# CPU_CIRCUIT.net
KiCad netlist of a schematic drawn in Altium Designer
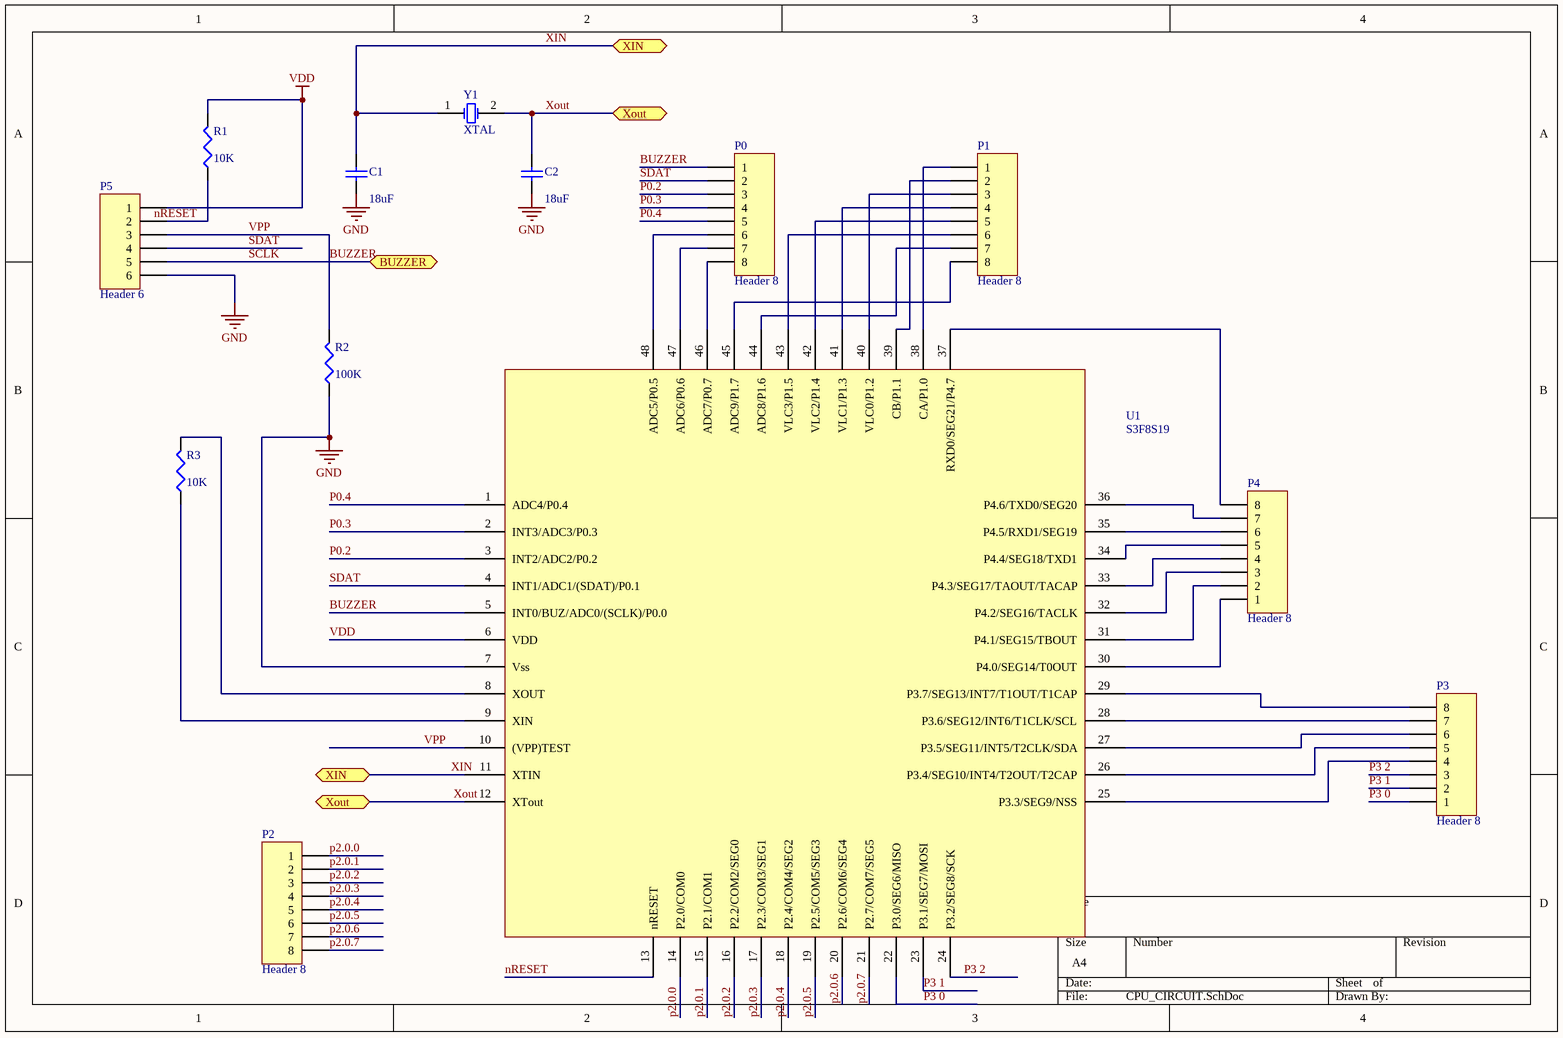
[diagram p0: CPU_CIRCUIT.SchDoc]

(export (version "E")
  (design (tool "Eeschema 10.0.6"))
  (components
    (comp (ref "C1")
      (value "18uF")
      (footprint "1608[0603]")
      (description "Capacitor (Semiconductor SIM Model)")
      (fields (field (name "Comment") "Cap Semi") (field (name "PUBLISHER") "Altium Limited"))
      (libsource (lib "Miscellaneous Devices") (part "Cap Semi"))
    )
    (comp (ref "C2")
      (value "18uF")
      (footprint "1608[0603]")
      (description "Capacitor (Semiconductor SIM Model)")
      (fields (field (name "Comment") "Cap Semi") (field (name "PUBLISHER") "Altium Limited"))
      (libsource (lib "Miscellaneous Devices") (part "Cap Semi"))
    )
    (comp (ref "P0")
      (value "Header 8")
      (footprint "HDR1X8")
      (description "Header, 8-Pin")
      (fields (field (name "PUBLISHER") "Altium Limited"))
      (libsource (lib "") (part "Header 8_1"))
    )
    (comp (ref "P1")
      (value "Header 8")
      (footprint "HDR1X8")
      (description "Header, 8-Pin")
      (fields (field (name "PUBLISHER") "Altium Limited"))
      (libsource (lib "") (part "Header 8_1"))
    )
    (comp (ref "P2")
      (value "Header 8")
      (footprint "HDR1X8")
      (description "Header, 8-Pin")
      (fields (field (name "PUBLISHER") "Altium Limited"))
      (libsource (lib "") (part "Header 8_2"))
    )
    (comp (ref "P3")
      (value "Header 8")
      (footprint "HDR1X8")
      (description "Header, 8-Pin")
      (fields (field (name "PUBLISHER") "Altium Limited"))
      (libsource (lib "Miscellaneous Connectors") (part "Header 8"))
    )
    (comp (ref "P4")
      (value "Header 8")
      (footprint "HDR1X8")
      (description "Header, 8-Pin")
      (fields (field (name "PUBLISHER") "Altium Limited"))
      (libsource (lib "Miscellaneous Connectors") (part "Header 8"))
    )
    (comp (ref "P5")
      (value "Header 6")
      (footprint "HDR1X6")
      (description "Header, 6-Pin")
      (fields (field (name "PUBLISHER") "Altium Limited"))
      (libsource (lib "Miscellaneous Connectors") (part "Header 6"))
    )
    (comp (ref "R1")
      (value "10K")
      (footprint "J1-0603")
      (description "Resistor")
      (fields (field (name "Comment") "Res3") (field (name "PUBLISHER") "Altium Limited"))
      (libsource (lib "Miscellaneous Devices") (part "Res3"))
    )
    (comp (ref "R2")
      (value "100K")
      (footprint "J1-0603")
      (description "Resistor")
      (fields (field (name "Comment") "Res3") (field (name "PUBLISHER") "Altium Limited"))
      (libsource (lib "Miscellaneous Devices") (part "Res3"))
    )
    (comp (ref "R3")
      (value "10K")
      (footprint "J1-0603")
      (description "Resistor")
      (fields (field (name "Comment") "Res3") (field (name "PUBLISHER") "Altium Limited"))
      (libsource (lib "Miscellaneous Devices") (part "Res3"))
    )
    (comp (ref "U1")
      (value "S3F8S19")
      (footprint "QFP75P1335X1335X230-48N")
      (libsource (lib "IOT_SCh") (part "S3F8S19"))
    )
    (comp (ref "Y1")
      (value "XTAL")
      (footprint "R38")
      (description "Crystal Oscillator")
      (fields (field (name "PUBLISHER") "Altium Limited"))
      (libsource (lib "Miscellaneous Devices") (part "XTAL"))
    )
  )
  (nets
    (net (code "1") (name "/BUZZER") (class "Default")
      (node (ref "P0") (pin "1") (pinfunction "1_1") (pintype "passive"))
      (node (ref "P5") (pin "3") (pinfunction "3_3") (pintype "passive"))
      (node (ref "P5") (pin "5") (pinfunction "5_5") (pintype "passive"))
      (node (ref "R2") (pin "2") (pinfunction "2_2") (pintype "passive"))
      (node (ref "U1") (pin "10") (pinfunction "(VPP)TEST_10") (pintype "passive"))
      (node (ref "U1") (pin "5") (pinfunction "INT0/BUZ/ADC0/(SCLK)/P0.0_5") (pintype "passive"))
    )
    (net (code "2") (name "/P0.2") (class "Default")
      (node (ref "P0") (pin "3") (pinfunction "3_3") (pintype "passive"))
      (node (ref "U1") (pin "3") (pinfunction "INT2/ADC2/P0.2_3") (pintype "passive"))
    )
    (net (code "3") (name "/P0.3") (class "Default")
      (node (ref "P0") (pin "4") (pinfunction "4_4") (pintype "passive"))
      (node (ref "U1") (pin "2") (pinfunction "INT3/ADC3/P0.3_2") (pintype "passive"))
    )
    (net (code "4") (name "/P0.4") (class "Default")
      (node (ref "P0") (pin "5") (pinfunction "5_5") (pintype "passive"))
      (node (ref "U1") (pin "1") (pinfunction "ADC4/P0.4_1") (pintype "passive"))
    )
    (net (code "5") (name "/P3 0") (class "Default")
      (node (ref "P3") (pin "1") (pinfunction "1_1") (pintype "passive"))
      (node (ref "U1") (pin "22") (pinfunction "P3.0/SEG6/MISO_22") (pintype "passive"))
    )
    (net (code "6") (name "/P3 1") (class "Default")
      (node (ref "P3") (pin "2") (pinfunction "2_2") (pintype "passive"))
      (node (ref "U1") (pin "23") (pinfunction "P3.1/SEG7/MOSI_23") (pintype "passive"))
    )
    (net (code "7") (name "/P3 2") (class "Default")
      (node (ref "P3") (pin "3") (pinfunction "3_3") (pintype "passive"))
      (node (ref "U1") (pin "24") (pinfunction "P3.2/SEG8/SCK_24") (pintype "passive"))
    )
    (net (code "8") (name "/SDAT") (class "Default")
      (node (ref "P0") (pin "2") (pinfunction "2_2") (pintype "passive"))
      (node (ref "P5") (pin "4") (pinfunction "4_4") (pintype "passive"))
      (node (ref "U1") (pin "4") (pinfunction "INT1/ADC1/(SDAT)/P0.1_4") (pintype "passive"))
    )
    (net (code "9") (name "/XIN") (class "Default")
      (node (ref "C1") (pin "2") (pinfunction "2_2") (pintype "passive"))
      (node (ref "U1") (pin "11") (pinfunction "XTIN_11") (pintype "passive"))
      (node (ref "Y1") (pin "1") (pinfunction "OSC1_1") (pintype "passive"))
    )
    (net (code "10") (name "/Xout") (class "Default")
      (node (ref "C2") (pin "2") (pinfunction "2_2") (pintype "passive"))
      (node (ref "U1") (pin "12") (pinfunction "XTout_12") (pintype "passive"))
      (node (ref "Y1") (pin "2") (pinfunction "OSC2_2") (pintype "passive"))
    )
    (net (code "11") (name "/nRESET") (class "Default")
      (node (ref "U1") (pin "13") (pinfunction "nRESET_13") (pintype "passive"))
    )
    (net (code "12") (name "/p2.0.0") (class "Default")
      (node (ref "P2") (pin "1") (pinfunction "1_1") (pintype "passive"))
      (node (ref "U1") (pin "14") (pinfunction "P2.0/COM0_14") (pintype "passive"))
    )
    (net (code "13") (name "/p2.0.1") (class "Default")
      (node (ref "P2") (pin "2") (pinfunction "2_2") (pintype "passive"))
      (node (ref "U1") (pin "15") (pinfunction "P2.1/COM1_15") (pintype "passive"))
    )
    (net (code "14") (name "/p2.0.2") (class "Default")
      (node (ref "P2") (pin "3") (pinfunction "3_3") (pintype "passive"))
      (node (ref "U1") (pin "16") (pinfunction "P2.2/COM2/SEG0_16") (pintype "passive"))
    )
    (net (code "15") (name "/p2.0.3") (class "Default")
      (node (ref "P2") (pin "4") (pinfunction "4_4") (pintype "passive"))
      (node (ref "U1") (pin "17") (pinfunction "P2.3/COM3/SEG1_17") (pintype "passive"))
    )
    (net (code "16") (name "/p2.0.4") (class "Default")
      (node (ref "P2") (pin "5") (pinfunction "5_5") (pintype "passive"))
      (node (ref "U1") (pin "18") (pinfunction "P2.4/COM4/SEG2_18") (pintype "passive"))
    )
    (net (code "17") (name "/p2.0.5") (class "Default")
      (node (ref "P2") (pin "6") (pinfunction "6_6") (pintype "passive"))
      (node (ref "U1") (pin "19") (pinfunction "P2.5/COM5/SEG3_19") (pintype "passive"))
    )
    (net (code "18") (name "/p2.0.6") (class "Default")
      (node (ref "P2") (pin "7") (pinfunction "7_7") (pintype "passive"))
      (node (ref "U1") (pin "20") (pinfunction "P2.6/COM6/SEG4_20") (pintype "passive"))
    )
    (net (code "19") (name "/p2.0.7") (class "Default")
      (node (ref "P2") (pin "8") (pinfunction "8_8") (pintype "passive"))
      (node (ref "U1") (pin "21") (pinfunction "P2.7/COM7/SEG5_21") (pintype "passive"))
    )
    (net (code "20") (name "GND") (class "Default")
      (node (ref "C1") (pin "1") (pinfunction "1_1") (pintype "passive"))
      (node (ref "C2") (pin "1") (pinfunction "1_1") (pintype "passive"))
      (node (ref "P5") (pin "6") (pinfunction "6_6") (pintype "passive"))
      (node (ref "R2") (pin "1") (pinfunction "1_1") (pintype "passive"))
      (node (ref "U1") (pin "7") (pinfunction "Vss_7") (pintype "passive"))
    )
    (net (code "21") (name "Net-(P5-Pad2)") (class "Default")
      (node (ref "P5") (pin "2") (pinfunction "2_2") (pintype "passive"))
      (node (ref "R1") (pin "1") (pinfunction "1_1") (pintype "passive"))
    )
    (net (code "22") (name "Net-(U1-ADC5{slash}P0.5)") (class "Default")
      (node (ref "P0") (pin "6") (pinfunction "6_6") (pintype "passive"))
      (node (ref "U1") (pin "48") (pinfunction "ADC5/P0.5_48") (pintype "passive"))
    )
    (net (code "23") (name "Net-(U1-ADC6{slash}P0.6)") (class "Default")
      (node (ref "P0") (pin "7") (pinfunction "7_7") (pintype "passive"))
      (node (ref "U1") (pin "47") (pinfunction "ADC6/P0.6_47") (pintype "passive"))
    )
    (net (code "24") (name "Net-(U1-ADC7{slash}P0.7)") (class "Default")
      (node (ref "P0") (pin "8") (pinfunction "8_8") (pintype "passive"))
      (node (ref "U1") (pin "46") (pinfunction "ADC7/P0.7_46") (pintype "passive"))
    )
    (net (code "25") (name "Net-(U1-ADC8{slash}P1.6)") (class "Default")
      (node (ref "P1") (pin "7") (pinfunction "7_7") (pintype "passive"))
      (node (ref "U1") (pin "44") (pinfunction "ADC8/P1.6_44") (pintype "passive"))
    )
    (net (code "26") (name "Net-(U1-ADC9{slash}P1.7)") (class "Default")
      (node (ref "P1") (pin "8") (pinfunction "8_8") (pintype "passive"))
      (node (ref "U1") (pin "45") (pinfunction "ADC9/P1.7_45") (pintype "passive"))
    )
    (net (code "27") (name "Net-(U1-CA{slash}P1.0)") (class "Default")
      (node (ref "P1") (pin "1") (pinfunction "1_1") (pintype "passive"))
      (node (ref "U1") (pin "38") (pinfunction "CA/P1.0_38") (pintype "passive"))
    )
    (net (code "28") (name "Net-(U1-CB{slash}P1.1)") (class "Default")
      (node (ref "P1") (pin "2") (pinfunction "2_2") (pintype "passive"))
      (node (ref "U1") (pin "39") (pinfunction "CB/P1.1_39") (pintype "passive"))
    )
    (net (code "29") (name "Net-(U1-P3.3{slash}SEG9{slash}NSS)") (class "Default")
      (node (ref "P3") (pin "4") (pinfunction "4_4") (pintype "passive"))
      (node (ref "U1") (pin "25") (pinfunction "P3.3/SEG9/NSS_25") (pintype "passive"))
    )
    (net (code "30") (name "Net-(U1-P3.4{slash}SEG10{slash}INT4{slash}T2OUT{slash}T2CAP)") (class "Default")
      (node (ref "P3") (pin "5") (pinfunction "5_5") (pintype "passive"))
      (node (ref "U1") (pin "26") (pinfunction "P3.4/SEG10/INT4/T2OUT/T2CAP_26") (pintype "passive"))
    )
    (net (code "31") (name "Net-(U1-P3.5{slash}SEG11{slash}INT5{slash}T2CLK{slash}SDA)") (class "Default")
      (node (ref "P3") (pin "6") (pinfunction "6_6") (pintype "passive"))
      (node (ref "U1") (pin "27") (pinfunction "P3.5/SEG11/INT5/T2CLK/SDA_27") (pintype "passive"))
    )
    (net (code "32") (name "Net-(U1-P3.6{slash}SEG12{slash}INT6{slash}T1CLK{slash}SCL)") (class "Default")
      (node (ref "P3") (pin "7") (pinfunction "7_7") (pintype "passive"))
      (node (ref "U1") (pin "28") (pinfunction "P3.6/SEG12/INT6/T1CLK/SCL_28") (pintype "passive"))
    )
    (net (code "33") (name "Net-(U1-P3.7{slash}SEG13{slash}INT7{slash}T1OUT{slash}T1CAP)") (class "Default")
      (node (ref "P3") (pin "8") (pinfunction "8_8") (pintype "passive"))
      (node (ref "U1") (pin "29") (pinfunction "P3.7/SEG13/INT7/T1OUT/T1CAP_29") (pintype "passive"))
    )
    (net (code "34") (name "Net-(U1-P4.0{slash}SEG14{slash}T0OUT)") (class "Default")
      (node (ref "P4") (pin "1") (pinfunction "1_1") (pintype "passive"))
      (node (ref "U1") (pin "30") (pinfunction "P4.0/SEG14/T0OUT_30") (pintype "passive"))
    )
    (net (code "35") (name "Net-(U1-P4.1{slash}SEG15{slash}TBOUT)") (class "Default")
      (node (ref "P4") (pin "2") (pinfunction "2_2") (pintype "passive"))
      (node (ref "U1") (pin "31") (pinfunction "P4.1/SEG15/TBOUT_31") (pintype "passive"))
    )
    (net (code "36") (name "Net-(U1-P4.2{slash}SEG16{slash}TACLK)") (class "Default")
      (node (ref "P4") (pin "3") (pinfunction "3_3") (pintype "passive"))
      (node (ref "U1") (pin "32") (pinfunction "P4.2/SEG16/TACLK_32") (pintype "passive"))
    )
    (net (code "37") (name "Net-(U1-P4.3{slash}SEG17{slash}TAOUT{slash}TACAP)") (class "Default")
      (node (ref "P4") (pin "4") (pinfunction "4_4") (pintype "passive"))
      (node (ref "U1") (pin "33") (pinfunction "P4.3/SEG17/TAOUT/TACAP_33") (pintype "passive"))
    )
    (net (code "38") (name "Net-(U1-P4.4{slash}SEG18{slash}TXD1)") (class "Default")
      (node (ref "P4") (pin "5") (pinfunction "5_5") (pintype "passive"))
      (node (ref "U1") (pin "34") (pinfunction "P4.4/SEG18/TXD1_34") (pintype "passive"))
    )
    (net (code "39") (name "Net-(U1-P4.5{slash}RXD1{slash}SEG19)") (class "Default")
      (node (ref "P4") (pin "6") (pinfunction "6_6") (pintype "passive"))
      (node (ref "U1") (pin "35") (pinfunction "P4.5/RXD1/SEG19_35") (pintype "passive"))
    )
    (net (code "40") (name "Net-(U1-P4.6{slash}TXD0{slash}SEG20)") (class "Default")
      (node (ref "P4") (pin "7") (pinfunction "7_7") (pintype "passive"))
      (node (ref "U1") (pin "36") (pinfunction "P4.6/TXD0/SEG20_36") (pintype "passive"))
    )
    (net (code "41") (name "Net-(U1-RXD0{slash}SEG21{slash}P4.7)") (class "Default")
      (node (ref "P4") (pin "8") (pinfunction "8_8") (pintype "passive"))
      (node (ref "U1") (pin "37") (pinfunction "RXD0/SEG21/P4.7_37") (pintype "passive"))
    )
    (net (code "42") (name "Net-(U1-VLC0{slash}P1.2)") (class "Default")
      (node (ref "P1") (pin "3") (pinfunction "3_3") (pintype "passive"))
      (node (ref "U1") (pin "40") (pinfunction "VLC0/P1.2_40") (pintype "passive"))
    )
    (net (code "43") (name "Net-(U1-VLC1{slash}P1.3)") (class "Default")
      (node (ref "P1") (pin "4") (pinfunction "4_4") (pintype "passive"))
      (node (ref "U1") (pin "41") (pinfunction "VLC1/P1.3_41") (pintype "passive"))
    )
    (net (code "44") (name "Net-(U1-VLC2{slash}P1.4)") (class "Default")
      (node (ref "P1") (pin "5") (pinfunction "5_5") (pintype "passive"))
      (node (ref "U1") (pin "42") (pinfunction "VLC2/P1.4_42") (pintype "passive"))
    )
    (net (code "45") (name "Net-(U1-VLC3{slash}P1.5)") (class "Default")
      (node (ref "P1") (pin "6") (pinfunction "6_6") (pintype "passive"))
      (node (ref "U1") (pin "43") (pinfunction "VLC3/P1.5_43") (pintype "passive"))
    )
    (net (code "46") (name "Net-(U1-XIN)") (class "Default")
      (node (ref "R3") (pin "1") (pinfunction "1_1") (pintype "passive"))
      (node (ref "U1") (pin "9") (pinfunction "XIN_9") (pintype "passive"))
    )
    (net (code "47") (name "Net-(U1-XOUT)") (class "Default")
      (node (ref "R3") (pin "2") (pinfunction "2_2") (pintype "passive"))
      (node (ref "U1") (pin "8") (pinfunction "XOUT_8") (pintype "passive"))
    )
    (net (code "48") (name "VDD") (class "Default")
      (node (ref "P5") (pin "1") (pinfunction "1_1") (pintype "passive"))
      (node (ref "R1") (pin "2") (pinfunction "2_2") (pintype "passive"))
      (node (ref "U1") (pin "6") (pinfunction "VDD_6") (pintype "passive"))
    )
  )
)
